# tmc4671_Output_Feedback.net
KiCad netlist of a schematic drawn in Altium Designer
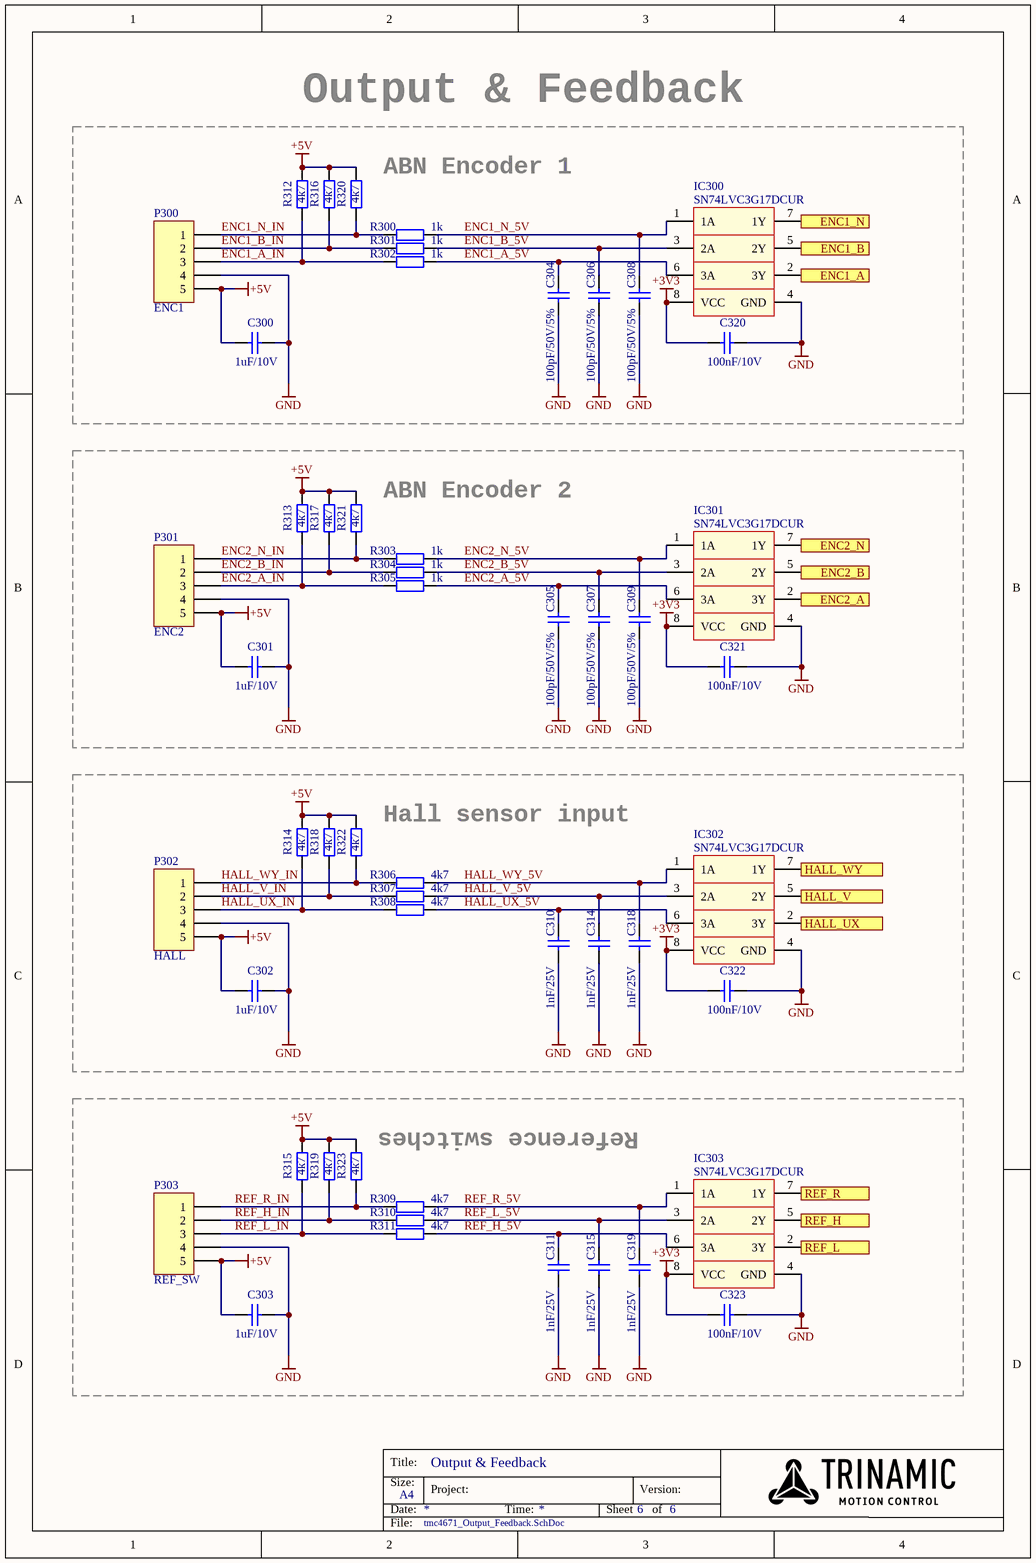
[diagram p0: tmc4671_Output_Feedback.SchDoc]

(export (version "E")
  (design (tool "Eeschema 10.0.6"))
  (components
    (comp (ref "C300")
      (value "1uF/10V")
      (footprint "C0603")
      (description "SMD Multilayer Ceramic Capacitor, 0603 [1608 Metric], 1 µF, 10 V, ± 10%, X5R, MC Series")
      (fields (field (name "MF") "MULTICOMP") (field (name "MPN") "MC0603X105K100CT"))
      (libsource (lib "SMD_Passives") (part "C, 1 µF, 10 V, ± 10%, X5R, MC Series, 0603 [1608 Metric]"))
    )
    (comp (ref "C301")
      (value "1uF/10V")
      (footprint "C0603")
      (description "SMD Multilayer Ceramic Capacitor, 0603 [1608 Metric], 1 µF, 10 V, ± 10%, X5R, MC Series")
      (fields (field (name "MF") "MULTICOMP") (field (name "MPN") "MC0603X105K100CT"))
      (libsource (lib "SMD_Passives") (part "C, 1 µF, 10 V, ± 10%, X5R, MC Series, 0603 [1608 Metric]"))
    )
    (comp (ref "C302")
      (value "1uF/10V")
      (footprint "C0603")
      (description "SMD Multilayer Ceramic Capacitor, 0603 [1608 Metric], 1 µF, 10 V, ± 10%, X5R, MC Series")
      (fields (field (name "MF") "MULTICOMP") (field (name "MPN") "MC0603X105K100CT"))
      (libsource (lib "SMD_Passives") (part "C, 1 µF, 10 V, ± 10%, X5R, MC Series, 0603 [1608 Metric]"))
    )
    (comp (ref "C303")
      (value "1uF/10V")
      (footprint "C0603")
      (description "SMD Multilayer Ceramic Capacitor, 0603 [1608 Metric], 1 µF, 10 V, ± 10%, X5R, MC Series")
      (fields (field (name "MF") "MULTICOMP") (field (name "MPN") "MC0603X105K100CT"))
      (libsource (lib "SMD_Passives") (part "C, 1 µF, 10 V, ± 10%, X5R, MC Series, 0603 [1608 Metric]"))
    )
    (comp (ref "C304")
      (value "100pF/50V/5%")
      (footprint "C0603")
      (description "SMD Multilayer Ceramic Capacitor, 0603 [1608 Metric], 100 pF, 50 V, ± 5%, C0G / NP0, MC Series")
      (fields (field (name "MF") "MULTICOMP") (field (name "MPN") "MC0603N101J500CT"))
      (libsource (lib "SMD_Passives") (part "C, 100 pF, 50 V, ± 5%, C0G / NP0, MC Series, 0603 [1608 Metric]"))
    )
    (comp (ref "C305")
      (value "100pF/50V/5%")
      (footprint "C0603")
      (description "SMD Multilayer Ceramic Capacitor, 0603 [1608 Metric], 100 pF, 50 V, ± 5%, C0G / NP0, MC Series")
      (fields (field (name "MF") "MULTICOMP") (field (name "MPN") "MC0603N101J500CT"))
      (libsource (lib "SMD_Passives") (part "C, 100 pF, 50 V, ± 5%, C0G / NP0, MC Series, 0603 [1608 Metric]"))
    )
    (comp (ref "C306")
      (value "100pF/50V/5%")
      (footprint "C0603")
      (description "SMD Multilayer Ceramic Capacitor, 0603 [1608 Metric], 100 pF, 50 V, ± 5%, C0G / NP0, MC Series")
      (fields (field (name "MF") "MULTICOMP") (field (name "MPN") "MC0603N101J500CT"))
      (libsource (lib "SMD_Passives") (part "C, 100 pF, 50 V, ± 5%, C0G / NP0, MC Series, 0603 [1608 Metric]"))
    )
    (comp (ref "C307")
      (value "100pF/50V/5%")
      (footprint "C0603")
      (description "SMD Multilayer Ceramic Capacitor, 0603 [1608 Metric], 100 pF, 50 V, ± 5%, C0G / NP0, MC Series")
      (fields (field (name "MF") "MULTICOMP") (field (name "MPN") "MC0603N101J500CT"))
      (libsource (lib "SMD_Passives") (part "C, 100 pF, 50 V, ± 5%, C0G / NP0, MC Series, 0603 [1608 Metric]"))
    )
    (comp (ref "C308")
      (value "100pF/50V/5%")
      (footprint "C0603")
      (description "SMD Multilayer Ceramic Capacitor, 0603 [1608 Metric], 100 pF, 50 V, ± 5%, C0G / NP0, MC Series")
      (fields (field (name "MF") "MULTICOMP") (field (name "MPN") "MC0603N101J500CT"))
      (libsource (lib "SMD_Passives") (part "C, 100 pF, 50 V, ± 5%, C0G / NP0, MC Series, 0603 [1608 Metric]"))
    )
    (comp (ref "C309")
      (value "100pF/50V/5%")
      (footprint "C0603")
      (description "SMD Multilayer Ceramic Capacitor, 0603 [1608 Metric], 100 pF, 50 V, ± 5%, C0G / NP0, MC Series")
      (fields (field (name "MF") "MULTICOMP") (field (name "MPN") "MC0603N101J500CT"))
      (libsource (lib "SMD_Passives") (part "C, 100 pF, 50 V, ± 5%, C0G / NP0, MC Series, 0603 [1608 Metric]"))
    )
    (comp (ref "C310")
      (value "1nF/25V")
      (footprint "C0603")
      (description "SMD Multilayer Ceramic Capacitor, 0603 [1608 Metric], 1000 pF, 25 V, ± 10%, X7R, MC Series")
      (fields (field (name "MF") "MULTICOMP") (field (name "MPN") "MC0603B102K250CT"))
      (libsource (lib "SMD_Passives") (part "C, 1nF, 25 V, ± 10%, X7R, MC Series, 0603 [1608 Metric]"))
    )
    (comp (ref "C311")
      (value "1nF/25V")
      (footprint "C0603")
      (description "SMD Multilayer Ceramic Capacitor, 0603 [1608 Metric], 1000 pF, 25 V, ± 10%, X7R, MC Series")
      (fields (field (name "MF") "MULTICOMP") (field (name "MPN") "MC0603B102K250CT"))
      (libsource (lib "SMD_Passives") (part "C, 1nF, 25 V, ± 10%, X7R, MC Series, 0603 [1608 Metric]"))
    )
    (comp (ref "C314")
      (value "1nF/25V")
      (footprint "C0603")
      (description "SMD Multilayer Ceramic Capacitor, 0603 [1608 Metric], 1000 pF, 25 V, ± 10%, X7R, MC Series")
      (fields (field (name "MF") "MULTICOMP") (field (name "MPN") "MC0603B102K250CT"))
      (libsource (lib "SMD_Passives") (part "C, 1nF, 25 V, ± 10%, X7R, MC Series, 0603 [1608 Metric]"))
    )
    (comp (ref "C315")
      (value "1nF/25V")
      (footprint "C0603")
      (description "SMD Multilayer Ceramic Capacitor, 0603 [1608 Metric], 1000 pF, 25 V, ± 10%, X7R, MC Series")
      (fields (field (name "MF") "MULTICOMP") (field (name "MPN") "MC0603B102K250CT"))
      (libsource (lib "SMD_Passives") (part "C, 1nF, 25 V, ± 10%, X7R, MC Series, 0603 [1608 Metric]"))
    )
    (comp (ref "C318")
      (value "1nF/25V")
      (footprint "C0603")
      (description "SMD Multilayer Ceramic Capacitor, 0603 [1608 Metric], 1000 pF, 25 V, ± 10%, X7R, MC Series")
      (fields (field (name "MF") "MULTICOMP") (field (name "MPN") "MC0603B102K250CT"))
      (libsource (lib "SMD_Passives") (part "C, 1nF, 25 V, ± 10%, X7R, MC Series, 0603 [1608 Metric]"))
    )
    (comp (ref "C319")
      (value "1nF/25V")
      (footprint "C0603")
      (description "SMD Multilayer Ceramic Capacitor, 0603 [1608 Metric], 1000 pF, 25 V, ± 10%, X7R, MC Series")
      (fields (field (name "MF") "MULTICOMP") (field (name "MPN") "MC0603B102K250CT"))
      (libsource (lib "SMD_Passives") (part "C, 1nF, 25 V, ± 10%, X7R, MC Series, 0603 [1608 Metric]"))
    )
    (comp (ref "C320")
      (value "100nF/10V")
      (footprint "C0603")
      (description "SMD Multilayer Ceramic Capacitor, 0603 [1608 Metric], 0.1 µF, 10 V, ± 10%, X7R, MC Series")
      (fields (field (name "MF") "Multicomp") (field (name "MPN") "MC0603B104K100CT"))
      (libsource (lib "SMD_Passives") (part "C, 0.1 µF, 10 V, ± 10%, X7R, 0603"))
    )
    (comp (ref "C321")
      (value "100nF/10V")
      (footprint "C0603")
      (description "SMD Multilayer Ceramic Capacitor, 0603 [1608 Metric], 0.1 µF, 10 V, ± 10%, X7R, MC Series")
      (fields (field (name "MF") "Multicomp") (field (name "MPN") "MC0603B104K100CT"))
      (libsource (lib "SMD_Passives") (part "C, 0.1 µF, 10 V, ± 10%, X7R, 0603"))
    )
    (comp (ref "C322")
      (value "100nF/10V")
      (footprint "C0603")
      (description "SMD Multilayer Ceramic Capacitor, 0603 [1608 Metric], 0.1 µF, 10 V, ± 10%, X7R, MC Series")
      (fields (field (name "MF") "Multicomp") (field (name "MPN") "MC0603B104K100CT"))
      (libsource (lib "SMD_Passives") (part "C, 0.1 µF, 10 V, ± 10%, X7R, 0603"))
    )
    (comp (ref "C323")
      (value "100nF/10V")
      (footprint "C0603")
      (description "SMD Multilayer Ceramic Capacitor, 0603 [1608 Metric], 0.1 µF, 10 V, ± 10%, X7R, MC Series")
      (fields (field (name "MF") "Multicomp") (field (name "MPN") "MC0603B104K100CT"))
      (libsource (lib "SMD_Passives") (part "C, 0.1 µF, 10 V, ± 10%, X7R, 0603"))
    )
    (comp (ref "IC300")
      (value "SN74LVC3G17DCUR")
      (footprint "TSSOP50P310X90-8L")
      (description "Triple Schmitt-Trigger Buffer, 74LVC3G17, 1.65 V to 5.5 V, VSSOP-8")
      (fields (field (name "MF") "TEXAS INSTRUMENTS"))
      (libsource (lib "TMC4671-EVAL_V1_0") (part "SN74LVC3G17DCUR"))
    )
    (comp (ref "IC301")
      (value "SN74LVC3G17DCUR")
      (footprint "TSSOP50P310X90-8L")
      (description "Triple Schmitt-Trigger Buffer, 74LVC3G17, 1.65 V to 5.5 V, VSSOP-8")
      (fields (field (name "MF") "TEXAS INSTRUMENTS"))
      (libsource (lib "TMC4671-EVAL_V1_0") (part "SN74LVC3G17DCUR"))
    )
    (comp (ref "IC302")
      (value "SN74LVC3G17DCUR")
      (footprint "TSSOP50P310X90-8L")
      (description "Triple Schmitt-Trigger Buffer, 74LVC3G17, 1.65 V to 5.5 V, VSSOP-8")
      (fields (field (name "MF") "TEXAS INSTRUMENTS"))
      (libsource (lib "TMC4671-EVAL_V1_0") (part "SN74LVC3G17DCUR"))
    )
    (comp (ref "IC303")
      (value "SN74LVC3G17DCUR")
      (footprint "TSSOP50P310X90-8L")
      (description "Triple Schmitt-Trigger Buffer, 74LVC3G17, 1.65 V to 5.5 V, VSSOP-8")
      (fields (field (name "MF") "TEXAS INSTRUMENTS"))
      (libsource (lib "TMC4671-EVAL_V1_0") (part "SN74LVC3G17DCUR"))
    )
    (comp (ref "P300")
      (value "ENC1")
      (footprint "TH_HDR_1X5")
      (description "Header, 5-Pin")
      (libsource (lib "Miscellaneous Connectors") (part "Header 5"))
    )
    (comp (ref "P301")
      (value "ENC2")
      (footprint "TH_HDR_1X5")
      (description "Header, 5-Pin")
      (libsource (lib "Miscellaneous Connectors") (part "Header 5"))
    )
    (comp (ref "P302")
      (value "HALL")
      (footprint "TH_HDR_1X5")
      (description "Header, 5-Pin")
      (libsource (lib "Miscellaneous Connectors") (part "Header 5"))
    )
    (comp (ref "P303")
      (value "REF_SW")
      (footprint "TH_HDR_1X5")
      (description "Header, 5-Pin")
      (libsource (lib "Miscellaneous Connectors") (part "Header 5"))
    )
    (comp (ref "R300")
      (value "1k")
      (footprint "R0603")
      (description "SMD Chip Resistor, Thick Film, 1 kohm, 50 V, 0603 [1608 Metric], 100 mW, ± 1%, MCWR Series")
      (fields
        (field (name "MPN") "MCWR06X1001FTL")
        (field (name "MF") "MULTICOMP")
        (field (name "RESISTANCE") "1k")
      )
      (libsource (lib "SMD_Passives") (part "R, 1 kohm, 50 V, 0603 [1608 Metric], 100mW, ± 1%, MCWR Series"))
    )
    (comp (ref "R301")
      (value "1k")
      (footprint "R0603")
      (description "SMD Chip Resistor, Thick Film, 1 kohm, 50 V, 0603 [1608 Metric], 100 mW, ± 1%, MCWR Series")
      (fields
        (field (name "MPN") "MCWR06X1001FTL")
        (field (name "MF") "MULTICOMP")
        (field (name "RESISTANCE") "1k")
      )
      (libsource (lib "SMD_Passives") (part "R, 1 kohm, 50 V, 0603 [1608 Metric], 100mW, ± 1%, MCWR Series"))
    )
    (comp (ref "R302")
      (value "1k")
      (footprint "R0603")
      (description "SMD Chip Resistor, Thick Film, 1 kohm, 50 V, 0603 [1608 Metric], 100 mW, ± 1%, MCWR Series")
      (fields
        (field (name "MPN") "MCWR06X1001FTL")
        (field (name "MF") "MULTICOMP")
        (field (name "RESISTANCE") "1k")
      )
      (libsource (lib "SMD_Passives") (part "R, 1 kohm, 50 V, 0603 [1608 Metric], 100mW, ± 1%, MCWR Series"))
    )
    (comp (ref "R303")
      (value "1k")
      (footprint "R0603")
      (description "SMD Chip Resistor, Thick Film, 1 kohm, 50 V, 0603 [1608 Metric], 100 mW, ± 1%, MCWR Series")
      (fields
        (field (name "MPN") "MCWR06X1001FTL")
        (field (name "MF") "MULTICOMP")
        (field (name "RESISTANCE") "1k")
      )
      (libsource (lib "SMD_Passives") (part "R, 1 kohm, 50 V, 0603 [1608 Metric], 100mW, ± 1%, MCWR Series"))
    )
    (comp (ref "R304")
      (value "1k")
      (footprint "R0603")
      (description "SMD Chip Resistor, Thick Film, 1 kohm, 50 V, 0603 [1608 Metric], 100 mW, ± 1%, MCWR Series")
      (fields
        (field (name "MPN") "MCWR06X1001FTL")
        (field (name "MF") "MULTICOMP")
        (field (name "RESISTANCE") "1k")
      )
      (libsource (lib "SMD_Passives") (part "R, 1 kohm, 50 V, 0603 [1608 Metric], 100mW, ± 1%, MCWR Series"))
    )
    (comp (ref "R305")
      (value "1k")
      (footprint "R0603")
      (description "SMD Chip Resistor, Thick Film, 1 kohm, 50 V, 0603 [1608 Metric], 100 mW, ± 1%, MCWR Series")
      (fields
        (field (name "MPN") "MCWR06X1001FTL")
        (field (name "MF") "MULTICOMP")
        (field (name "RESISTANCE") "1k")
      )
      (libsource (lib "SMD_Passives") (part "R, 1 kohm, 50 V, 0603 [1608 Metric], 100mW, ± 1%, MCWR Series"))
    )
    (comp (ref "R306")
      (value "4k7")
      (footprint "R0603")
      (description "SMD Chip Resistor, 4.7 kohm, 75 V, 0603 [1608 Metric], 100 mW, ± 1%, WR06 Series")
      (fields
        (field (name "MPN") "WR06X4701FTL")
        (field (name "MF") "WALSIN")
        (field (name "RESISTANCE") "4k7")
      )
      (libsource (lib "") (part "R, 4.7 kohm, 75 V, 0603 [1608 Metric], 100 mW, ± 1%, WR06 Series_1"))
    )
    (comp (ref "R307")
      (value "4k7")
      (footprint "R0603")
      (description "SMD Chip Resistor, 4.7 kohm, 75 V, 0603 [1608 Metric], 100 mW, ± 1%, WR06 Series")
      (fields
        (field (name "MPN") "WR06X4701FTL")
        (field (name "MF") "WALSIN")
        (field (name "RESISTANCE") "4k7")
      )
      (libsource (lib "") (part "R, 4.7 kohm, 75 V, 0603 [1608 Metric], 100 mW, ± 1%, WR06 Series_1"))
    )
    (comp (ref "R308")
      (value "4k7")
      (footprint "R0603")
      (description "SMD Chip Resistor, 4.7 kohm, 75 V, 0603 [1608 Metric], 100 mW, ± 1%, WR06 Series")
      (fields
        (field (name "MPN") "WR06X4701FTL")
        (field (name "MF") "WALSIN")
        (field (name "RESISTANCE") "4k7")
      )
      (libsource (lib "") (part "R, 4.7 kohm, 75 V, 0603 [1608 Metric], 100 mW, ± 1%, WR06 Series_1"))
    )
    (comp (ref "R309")
      (value "4k7")
      (footprint "R0603")
      (description "SMD Chip Resistor, 4.7 kohm, 75 V, 0603 [1608 Metric], 100 mW, ± 1%, WR06 Series")
      (fields
        (field (name "MPN") "WR06X4701FTL")
        (field (name "MF") "WALSIN")
        (field (name "RESISTANCE") "4k7")
      )
      (libsource (lib "") (part "R, 4.7 kohm, 75 V, 0603 [1608 Metric], 100 mW, ± 1%, WR06 Series_1"))
    )
    (comp (ref "R310")
      (value "4k7")
      (footprint "R0603")
      (description "SMD Chip Resistor, 4.7 kohm, 75 V, 0603 [1608 Metric], 100 mW, ± 1%, WR06 Series")
      (fields
        (field (name "MPN") "WR06X4701FTL")
        (field (name "MF") "WALSIN")
        (field (name "RESISTANCE") "4k7")
      )
      (libsource (lib "") (part "R, 4.7 kohm, 75 V, 0603 [1608 Metric], 100 mW, ± 1%, WR06 Series_1"))
    )
    (comp (ref "R311")
      (value "4k7")
      (footprint "R0603")
      (description "SMD Chip Resistor, 4.7 kohm, 75 V, 0603 [1608 Metric], 100 mW, ± 1%, WR06 Series")
      (fields
        (field (name "MPN") "WR06X4701FTL")
        (field (name "MF") "WALSIN")
        (field (name "RESISTANCE") "4k7")
      )
      (libsource (lib "") (part "R, 4.7 kohm, 75 V, 0603 [1608 Metric], 100 mW, ± 1%, WR06 Series_1"))
    )
    (comp (ref "R312")
      (value "4k7")
      (footprint "R0603")
      (description "SMD Chip Resistor, 4.7 kohm, 75 V, 0603 [1608 Metric], 100 mW, ± 1%, WR06 Series")
      (fields
        (field (name "MPN") "WR06X4701FTL")
        (field (name "MF") "WALSIN")
        (field (name "RESISTANCE") "4k7")
      )
      (libsource (lib "SMD_Passives") (part "R, 4.7 kohm, 75 V, 0603 [1608 Metric], 100 mW, ± 1%, WR06 Series"))
    )
    (comp (ref "R313")
      (value "4k7")
      (footprint "R0603")
      (description "SMD Chip Resistor, 4.7 kohm, 75 V, 0603 [1608 Metric], 100 mW, ± 1%, WR06 Series")
      (fields
        (field (name "MPN") "WR06X4701FTL")
        (field (name "MF") "WALSIN")
        (field (name "RESISTANCE") "4k7")
      )
      (libsource (lib "SMD_Passives") (part "R, 4.7 kohm, 75 V, 0603 [1608 Metric], 100 mW, ± 1%, WR06 Series"))
    )
    (comp (ref "R314")
      (value "4k7")
      (footprint "R0603")
      (description "SMD Chip Resistor, 4.7 kohm, 75 V, 0603 [1608 Metric], 100 mW, ± 1%, WR06 Series")
      (fields
        (field (name "MPN") "WR06X4701FTL")
        (field (name "MF") "WALSIN")
        (field (name "RESISTANCE") "4k7")
      )
      (libsource (lib "SMD_Passives") (part "R, 4.7 kohm, 75 V, 0603 [1608 Metric], 100 mW, ± 1%, WR06 Series"))
    )
    (comp (ref "R315")
      (value "4k7")
      (footprint "R0603")
      (description "SMD Chip Resistor, 4.7 kohm, 75 V, 0603 [1608 Metric], 100 mW, ± 1%, WR06 Series")
      (fields
        (field (name "MPN") "WR06X4701FTL")
        (field (name "MF") "WALSIN")
        (field (name "RESISTANCE") "4k7")
      )
      (libsource (lib "SMD_Passives") (part "R, 4.7 kohm, 75 V, 0603 [1608 Metric], 100 mW, ± 1%, WR06 Series"))
    )
    (comp (ref "R316")
      (value "4k7")
      (footprint "R0603")
      (description "SMD Chip Resistor, 4.7 kohm, 75 V, 0603 [1608 Metric], 100 mW, ± 1%, WR06 Series")
      (fields
        (field (name "MPN") "WR06X4701FTL")
        (field (name "MF") "WALSIN")
        (field (name "RESISTANCE") "4k7")
      )
      (libsource (lib "SMD_Passives") (part "R, 4.7 kohm, 75 V, 0603 [1608 Metric], 100 mW, ± 1%, WR06 Series"))
    )
    (comp (ref "R317")
      (value "4k7")
      (footprint "R0603")
      (description "SMD Chip Resistor, 4.7 kohm, 75 V, 0603 [1608 Metric], 100 mW, ± 1%, WR06 Series")
      (fields
        (field (name "MPN") "WR06X4701FTL")
        (field (name "MF") "WALSIN")
        (field (name "RESISTANCE") "4k7")
      )
      (libsource (lib "SMD_Passives") (part "R, 4.7 kohm, 75 V, 0603 [1608 Metric], 100 mW, ± 1%, WR06 Series"))
    )
    (comp (ref "R318")
      (value "4k7")
      (footprint "R0603")
      (description "SMD Chip Resistor, 4.7 kohm, 75 V, 0603 [1608 Metric], 100 mW, ± 1%, WR06 Series")
      (fields
        (field (name "MPN") "WR06X4701FTL")
        (field (name "MF") "WALSIN")
        (field (name "RESISTANCE") "4k7")
      )
      (libsource (lib "SMD_Passives") (part "R, 4.7 kohm, 75 V, 0603 [1608 Metric], 100 mW, ± 1%, WR06 Series"))
    )
    (comp (ref "R319")
      (value "4k7")
      (footprint "R0603")
      (description "SMD Chip Resistor, 4.7 kohm, 75 V, 0603 [1608 Metric], 100 mW, ± 1%, WR06 Series")
      (fields
        (field (name "MPN") "WR06X4701FTL")
        (field (name "MF") "WALSIN")
        (field (name "RESISTANCE") "4k7")
      )
      (libsource (lib "SMD_Passives") (part "R, 4.7 kohm, 75 V, 0603 [1608 Metric], 100 mW, ± 1%, WR06 Series"))
    )
    (comp (ref "R320")
      (value "4k7")
      (footprint "R0603")
      (description "SMD Chip Resistor, 4.7 kohm, 75 V, 0603 [1608 Metric], 100 mW, ± 1%, WR06 Series")
      (fields
        (field (name "MPN") "WR06X4701FTL")
        (field (name "MF") "WALSIN")
        (field (name "RESISTANCE") "4k7")
      )
      (libsource (lib "SMD_Passives") (part "R, 4.7 kohm, 75 V, 0603 [1608 Metric], 100 mW, ± 1%, WR06 Series"))
    )
    (comp (ref "R321")
      (value "4k7")
      (footprint "R0603")
      (description "SMD Chip Resistor, 4.7 kohm, 75 V, 0603 [1608 Metric], 100 mW, ± 1%, WR06 Series")
      (fields
        (field (name "MPN") "WR06X4701FTL")
        (field (name "MF") "WALSIN")
        (field (name "RESISTANCE") "4k7")
      )
      (libsource (lib "SMD_Passives") (part "R, 4.7 kohm, 75 V, 0603 [1608 Metric], 100 mW, ± 1%, WR06 Series"))
    )
    (comp (ref "R322")
      (value "4k7")
      (footprint "R0603")
      (description "SMD Chip Resistor, 4.7 kohm, 75 V, 0603 [1608 Metric], 100 mW, ± 1%, WR06 Series")
      (fields
        (field (name "MPN") "WR06X4701FTL")
        (field (name "MF") "WALSIN")
        (field (name "RESISTANCE") "4k7")
      )
      (libsource (lib "SMD_Passives") (part "R, 4.7 kohm, 75 V, 0603 [1608 Metric], 100 mW, ± 1%, WR06 Series"))
    )
    (comp (ref "R323")
      (value "4k7")
      (footprint "R0603")
      (description "SMD Chip Resistor, 4.7 kohm, 75 V, 0603 [1608 Metric], 100 mW, ± 1%, WR06 Series")
      (fields
        (field (name "MPN") "WR06X4701FTL")
        (field (name "MF") "WALSIN")
        (field (name "RESISTANCE") "4k7")
      )
      (libsource (lib "SMD_Passives") (part "R, 4.7 kohm, 75 V, 0603 [1608 Metric], 100 mW, ± 1%, WR06 Series"))
    )
  )
  (nets
    (net (code "1") (name "+3V3") (class "Default")
      (node (ref "C320") (pin "2") (pinfunction "2_2") (pintype "passive"))
      (node (ref "C321") (pin "2") (pinfunction "2_2") (pintype "passive"))
      (node (ref "C322") (pin "2") (pinfunction "2_2") (pintype "passive"))
      (node (ref "C323") (pin "2") (pinfunction "2_2") (pintype "passive"))
      (node (ref "IC300") (pin "8") (pinfunction "VCC_8") (pintype "power_in"))
      (node (ref "IC301") (pin "8") (pinfunction "VCC_8") (pintype "power_in"))
      (node (ref "IC302") (pin "8") (pinfunction "VCC_8") (pintype "power_in"))
      (node (ref "IC303") (pin "8") (pinfunction "VCC_8") (pintype "power_in"))
    )
    (net (code "2") (name "+5V") (class "Default")
      (node (ref "C300") (pin "2") (pinfunction "2_2") (pintype "passive"))
      (node (ref "C301") (pin "2") (pinfunction "2_2") (pintype "passive"))
      (node (ref "C302") (pin "2") (pinfunction "2_2") (pintype "passive"))
      (node (ref "C303") (pin "2") (pinfunction "2_2") (pintype "passive"))
      (node (ref "P300") (pin "5") (pinfunction "5_5") (pintype "passive"))
      (node (ref "P301") (pin "5") (pinfunction "5_5") (pintype "passive"))
      (node (ref "P302") (pin "5") (pinfunction "5_5") (pintype "passive"))
      (node (ref "P303") (pin "5") (pinfunction "5_5") (pintype "passive"))
      (node (ref "R312") (pin "2") (pinfunction "2_2") (pintype "passive"))
      (node (ref "R313") (pin "2") (pinfunction "2_2") (pintype "passive"))
      (node (ref "R314") (pin "2") (pinfunction "2_2") (pintype "passive"))
      (node (ref "R315") (pin "2") (pinfunction "2_2") (pintype "passive"))
      (node (ref "R316") (pin "2") (pinfunction "2_2") (pintype "passive"))
      (node (ref "R317") (pin "2") (pinfunction "2_2") (pintype "passive"))
      (node (ref "R318") (pin "2") (pinfunction "2_2") (pintype "passive"))
      (node (ref "R319") (pin "2") (pinfunction "2_2") (pintype "passive"))
      (node (ref "R320") (pin "2") (pinfunction "2_2") (pintype "passive"))
      (node (ref "R321") (pin "2") (pinfunction "2_2") (pintype "passive"))
      (node (ref "R322") (pin "2") (pinfunction "2_2") (pintype "passive"))
      (node (ref "R323") (pin "2") (pinfunction "2_2") (pintype "passive"))
    )
    (net (code "3") (name "/ENC1_A") (class "Default")
      (node (ref "IC300") (pin "2") (pinfunction "3Y_2") (pintype "power_in"))
    )
    (net (code "4") (name "/ENC1_A_5V") (class "Default")
      (node (ref "C304") (pin "2") (pinfunction "2_2") (pintype "passive"))
      (node (ref "IC300") (pin "6") (pinfunction "3A_6") (pintype "power_in"))
      (node (ref "R302") (pin "2") (pinfunction "2_2") (pintype "passive"))
    )
    (net (code "5") (name "/ENC1_A_IN") (class "Default")
      (node (ref "P300") (pin "3") (pinfunction "3_3") (pintype "passive"))
      (node (ref "R302") (pin "1") (pinfunction "1_1") (pintype "passive"))
      (node (ref "R312") (pin "1") (pinfunction "1_1") (pintype "passive"))
    )
    (net (code "6") (name "/ENC1_B") (class "Default")
      (node (ref "IC300") (pin "5") (pinfunction "2Y_5") (pintype "power_in"))
    )
    (net (code "7") (name "/ENC1_B_5V") (class "Default")
      (node (ref "C306") (pin "2") (pinfunction "2_2") (pintype "passive"))
      (node (ref "IC300") (pin "3") (pinfunction "2A_3") (pintype "power_in"))
      (node (ref "R301") (pin "2") (pinfunction "2_2") (pintype "passive"))
    )
    (net (code "8") (name "/ENC1_B_IN") (class "Default")
      (node (ref "P300") (pin "2") (pinfunction "2_2") (pintype "passive"))
      (node (ref "R301") (pin "1") (pinfunction "1_1") (pintype "passive"))
      (node (ref "R316") (pin "1") (pinfunction "1_1") (pintype "passive"))
    )
    (net (code "9") (name "/ENC1_N") (class "Default")
      (node (ref "IC300") (pin "7") (pinfunction "1Y_7") (pintype "power_in"))
    )
    (net (code "10") (name "/ENC1_N_5V") (class "Default")
      (node (ref "C308") (pin "2") (pinfunction "2_2") (pintype "passive"))
      (node (ref "IC300") (pin "1") (pinfunction "1A_1") (pintype "power_in"))
      (node (ref "R300") (pin "2") (pinfunction "2_2") (pintype "passive"))
    )
    (net (code "11") (name "/ENC1_N_IN") (class "Default")
      (node (ref "P300") (pin "1") (pinfunction "1_1") (pintype "passive"))
      (node (ref "R300") (pin "1") (pinfunction "1_1") (pintype "passive"))
      (node (ref "R320") (pin "1") (pinfunction "1_1") (pintype "passive"))
    )
    (net (code "12") (name "/ENC2_A") (class "Default")
      (node (ref "IC301") (pin "2") (pinfunction "3Y_2") (pintype "power_in"))
    )
    (net (code "13") (name "/ENC2_A_5V") (class "Default")
      (node (ref "C305") (pin "2") (pinfunction "2_2") (pintype "passive"))
      (node (ref "IC301") (pin "6") (pinfunction "3A_6") (pintype "power_in"))
      (node (ref "R305") (pin "2") (pinfunction "2_2") (pintype "passive"))
    )
    (net (code "14") (name "/ENC2_A_IN") (class "Default")
      (node (ref "P301") (pin "3") (pinfunction "3_3") (pintype "passive"))
      (node (ref "R305") (pin "1") (pinfunction "1_1") (pintype "passive"))
      (node (ref "R313") (pin "1") (pinfunction "1_1") (pintype "passive"))
    )
    (net (code "15") (name "/ENC2_B") (class "Default")
      (node (ref "IC301") (pin "5") (pinfunction "2Y_5") (pintype "power_in"))
    )
    (net (code "16") (name "/ENC2_B_5V") (class "Default")
      (node (ref "C307") (pin "2") (pinfunction "2_2") (pintype "passive"))
      (node (ref "IC301") (pin "3") (pinfunction "2A_3") (pintype "power_in"))
      (node (ref "R304") (pin "2") (pinfunction "2_2") (pintype "passive"))
    )
    (net (code "17") (name "/ENC2_B_IN") (class "Default")
      (node (ref "P301") (pin "2") (pinfunction "2_2") (pintype "passive"))
      (node (ref "R304") (pin "1") (pinfunction "1_1") (pintype "passive"))
      (node (ref "R317") (pin "1") (pinfunction "1_1") (pintype "passive"))
    )
    (net (code "18") (name "/ENC2_N") (class "Default")
      (node (ref "IC301") (pin "7") (pinfunction "1Y_7") (pintype "power_in"))
    )
    (net (code "19") (name "/ENC2_N_5V") (class "Default")
      (node (ref "C309") (pin "2") (pinfunction "2_2") (pintype "passive"))
      (node (ref "IC301") (pin "1") (pinfunction "1A_1") (pintype "power_in"))
      (node (ref "R303") (pin "2") (pinfunction "2_2") (pintype "passive"))
    )
    (net (code "20") (name "/ENC2_N_IN") (class "Default")
      (node (ref "P301") (pin "1") (pinfunction "1_1") (pintype "passive"))
      (node (ref "R303") (pin "1") (pinfunction "1_1") (pintype "passive"))
      (node (ref "R321") (pin "1") (pinfunction "1_1") (pintype "passive"))
    )
    (net (code "21") (name "/HALL_UX") (class "Default")
      (node (ref "IC302") (pin "2") (pinfunction "3Y_2") (pintype "power_in"))
    )
    (net (code "22") (name "/HALL_UX_5V") (class "Default")
      (node (ref "C310") (pin "2") (pinfunction "2_2") (pintype "passive"))
      (node (ref "IC302") (pin "6") (pinfunction "3A_6") (pintype "power_in"))
      (node (ref "R308") (pin "1") (pinfunction "1_1") (pintype "passive"))
    )
    (net (code "23") (name "/HALL_UX_IN") (class "Default")
      (node (ref "P302") (pin "3") (pinfunction "3_3") (pintype "passive"))
      (node (ref "R308") (pin "2") (pinfunction "2_2") (pintype "passive"))
      (node (ref "R314") (pin "1") (pinfunction "1_1") (pintype "passive"))
    )
    (net (code "24") (name "/HALL_V") (class "Default")
      (node (ref "IC302") (pin "5") (pinfunction "2Y_5") (pintype "power_in"))
    )
    (net (code "25") (name "/HALL_V_5V") (class "Default")
      (node (ref "C314") (pin "2") (pinfunction "2_2") (pintype "passive"))
      (node (ref "IC302") (pin "3") (pinfunction "2A_3") (pintype "power_in"))
      (node (ref "R307") (pin "1") (pinfunction "1_1") (pintype "passive"))
    )
    (net (code "26") (name "/HALL_V_IN") (class "Default")
      (node (ref "P302") (pin "2") (pinfunction "2_2") (pintype "passive"))
      (node (ref "R307") (pin "2") (pinfunction "2_2") (pintype "passive"))
      (node (ref "R318") (pin "1") (pinfunction "1_1") (pintype "passive"))
    )
    (net (code "27") (name "/HALL_WY") (class "Default")
      (node (ref "IC302") (pin "7") (pinfunction "1Y_7") (pintype "power_in"))
    )
    (net (code "28") (name "/HALL_WY_5V") (class "Default")
      (node (ref "C318") (pin "2") (pinfunction "2_2") (pintype "passive"))
      (node (ref "IC302") (pin "1") (pinfunction "1A_1") (pintype "power_in"))
      (node (ref "R306") (pin "1") (pinfunction "1_1") (pintype "passive"))
    )
    (net (code "29") (name "/HALL_WY_IN") (class "Default")
      (node (ref "P302") (pin "1") (pinfunction "1_1") (pintype "passive"))
      (node (ref "R306") (pin "2") (pinfunction "2_2") (pintype "passive"))
      (node (ref "R322") (pin "1") (pinfunction "1_1") (pintype "passive"))
    )
    (net (code "30") (name "/REF_H") (class "Default")
      (node (ref "IC303") (pin "5") (pinfunction "2Y_5") (pintype "power_in"))
    )
    (net (code "31") (name "/REF_H_5V") (class "Default")
      (node (ref "C311") (pin "2") (pinfunction "2_2") (pintype "passive"))
      (node (ref "IC303") (pin "6") (pinfunction "3A_6") (pintype "power_in"))
      (node (ref "R311") (pin "1") (pinfunction "1_1") (pintype "passive"))
    )
    (net (code "32") (name "/REF_H_IN") (class "Default")
      (node (ref "P303") (pin "2") (pinfunction "2_2") (pintype "passive"))
      (node (ref "R310") (pin "2") (pinfunction "2_2") (pintype "passive"))
      (node (ref "R319") (pin "1") (pinfunction "1_1") (pintype "passive"))
    )
    (net (code "33") (name "/REF_L") (class "Default")
      (node (ref "IC303") (pin "2") (pinfunction "3Y_2") (pintype "power_in"))
    )
    (net (code "34") (name "/REF_L_5V") (class "Default")
      (node (ref "C315") (pin "2") (pinfunction "2_2") (pintype "passive"))
      (node (ref "IC303") (pin "3") (pinfunction "2A_3") (pintype "power_in"))
      (node (ref "R310") (pin "1") (pinfunction "1_1") (pintype "passive"))
    )
    (net (code "35") (name "/REF_L_IN") (class "Default")
      (node (ref "P303") (pin "3") (pinfunction "3_3") (pintype "passive"))
      (node (ref "R311") (pin "2") (pinfunction "2_2") (pintype "passive"))
      (node (ref "R315") (pin "1") (pinfunction "1_1") (pintype "passive"))
    )
    (net (code "36") (name "/REF_R") (class "Default")
      (node (ref "IC303") (pin "7") (pinfunction "1Y_7") (pintype "power_in"))
    )
    (net (code "37") (name "/REF_R_5V") (class "Default")
      (node (ref "C319") (pin "2") (pinfunction "2_2") (pintype "passive"))
      (node (ref "IC303") (pin "1") (pinfunction "1A_1") (pintype "power_in"))
      (node (ref "R309") (pin "1") (pinfunction "1_1") (pintype "passive"))
    )
    (net (code "38") (name "/REF_R_IN") (class "Default")
      (node (ref "P303") (pin "1") (pinfunction "1_1") (pintype "passive"))
      (node (ref "R309") (pin "2") (pinfunction "2_2") (pintype "passive"))
      (node (ref "R323") (pin "1") (pinfunction "1_1") (pintype "passive"))
    )
    (net (code "39") (name "GND") (class "Default")
      (node (ref "C300") (pin "1") (pinfunction "1_1") (pintype "passive"))
      (node (ref "C301") (pin "1") (pinfunction "1_1") (pintype "passive"))
      (node (ref "C302") (pin "1") (pinfunction "1_1") (pintype "passive"))
      (node (ref "C303") (pin "1") (pinfunction "1_1") (pintype "passive"))
      (node (ref "C304") (pin "1") (pinfunction "1_1") (pintype "passive"))
      (node (ref "C305") (pin "1") (pinfunction "1_1") (pintype "passive"))
      (node (ref "C306") (pin "1") (pinfunction "1_1") (pintype "passive"))
      (node (ref "C307") (pin "1") (pinfunction "1_1") (pintype "passive"))
      (node (ref "C308") (pin "1") (pinfunction "1_1") (pintype "passive"))
      (node (ref "C309") (pin "1") (pinfunction "1_1") (pintype "passive"))
      (node (ref "C310") (pin "1") (pinfunction "1_1") (pintype "passive"))
      (node (ref "C311") (pin "1") (pinfunction "1_1") (pintype "passive"))
      (node (ref "C314") (pin "1") (pinfunction "1_1") (pintype "passive"))
      (node (ref "C315") (pin "1") (pinfunction "1_1") (pintype "passive"))
      (node (ref "C318") (pin "1") (pinfunction "1_1") (pintype "passive"))
      (node (ref "C319") (pin "1") (pinfunction "1_1") (pintype "passive"))
      (node (ref "C320") (pin "1") (pinfunction "1_1") (pintype "passive"))
      (node (ref "C321") (pin "1") (pinfunction "1_1") (pintype "passive"))
      (node (ref "C322") (pin "1") (pinfunction "1_1") (pintype "passive"))
      (node (ref "C323") (pin "1") (pinfunction "1_1") (pintype "passive"))
      (node (ref "IC300") (pin "4") (pinfunction "GND_4") (pintype "power_in"))
      (node (ref "IC301") (pin "4") (pinfunction "GND_4") (pintype "power_in"))
      (node (ref "IC302") (pin "4") (pinfunction "GND_4") (pintype "power_in"))
      (node (ref "IC303") (pin "4") (pinfunction "GND_4") (pintype "power_in"))
      (node (ref "P300") (pin "4") (pinfunction "4_4") (pintype "passive"))
      (node (ref "P301") (pin "4") (pinfunction "4_4") (pintype "passive"))
      (node (ref "P302") (pin "4") (pinfunction "4_4") (pintype "passive"))
      (node (ref "P303") (pin "4") (pinfunction "4_4") (pintype "passive"))
    )
  )
)
